# Esquem_tico_01.net
KiCad netlist of a schematic drawn in EAGLE
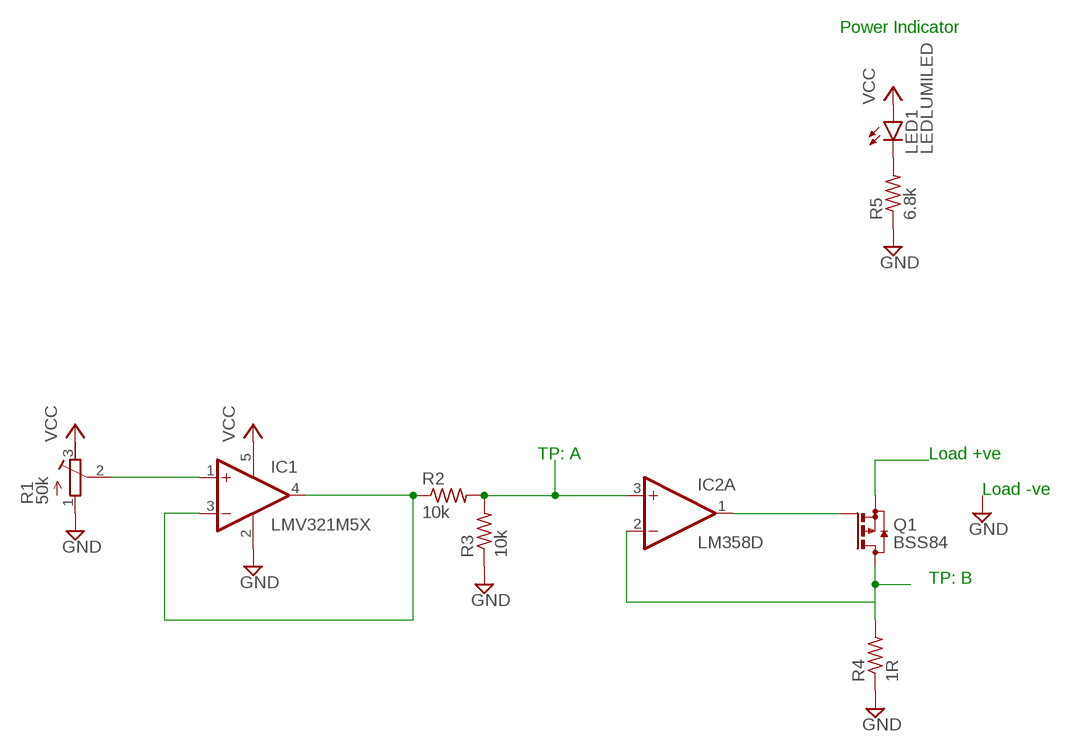
[diagram p0: schematic, sheet 1]

(export (version "E")
  (design (tool "Eeschema 10.0.6"))
  (components
    (comp (ref "IC1")
      (value "LMV321M5X")
      (footprint "eagle-import:SOT23-5")
      (libsource (lib "eagle-import") (part "LMV321?M5X"))
    )
    (comp (ref "IC2")
      (value "LM358D")
      (footprint "eagle-import:SO08")
      (libsource (lib "eagle-import") (part "LM358D"))
    )
    (comp (ref "LED1")
      (value "LEDLUMILED")
      (footprint "eagle-import:LUMILED")
      (libsource (lib "eagle-import") (part "LEDLUMILED"))
    )
    (comp (ref "Q1")
      (value "BSS84")
      (footprint "eagle-import:SOT23")
      (libsource (lib "eagle-import") (part "BSS84"))
    )
    (comp (ref "R1")
      (value "50k")
      (footprint "eagle-import:RTRIM3339P")
      (libsource (lib "eagle-import") (part "R-TRIMM3339P"))
    )
    (comp (ref "R2")
      (value "10k")
      (footprint "eagle-import:0207_10")
      (libsource (lib "eagle-import") (part "R-US_0207/10"))
    )
    (comp (ref "R3")
      (value "10k")
      (footprint "eagle-import:0207_10")
      (libsource (lib "eagle-import") (part "R-US_0207/10"))
    )
    (comp (ref "R4")
      (value "1R")
      (footprint "eagle-import:0207_10")
      (libsource (lib "eagle-import") (part "R-US_0207/10"))
    )
    (comp (ref "R5")
      (value "6.8k")
      (footprint "eagle-import:0207_10")
      (libsource (lib "eagle-import") (part "R-US_0207/10"))
    )
  )
  (nets
    (net (code "1") (name "GND") (class "Default")
      (node (ref "IC1") (pin "2") (pinfunction "V-_2") (pintype "power_in"))
      (node (ref "R1") (pin "1") (pinfunction "A_1") (pintype "passive"))
      (node (ref "R3") (pin "1") (pinfunction "1_1") (pintype "passive"))
      (node (ref "R4") (pin "1") (pinfunction "1_1") (pintype "passive"))
      (node (ref "R5") (pin "1") (pinfunction "1_1") (pintype "passive"))
    )
    (net (code "2") (name "Net-(IC1-+IN)") (class "Default")
      (node (ref "IC1") (pin "1") (pinfunction "+IN_1") (pintype "input"))
      (node (ref "R1") (pin "2") (pinfunction "S_2") (pintype "passive"))
    )
    (net (code "3") (name "Net-(IC1--IN)") (class "Default")
      (node (ref "IC1") (pin "3") (pinfunction "-IN_3") (pintype "input"))
      (node (ref "IC1") (pin "4") (pinfunction "OUT_4") (pintype "output"))
      (node (ref "R2") (pin "1") (pinfunction "1_1") (pintype "passive"))
    )
    (net (code "4") (name "Net-(IC2A-+IN)") (class "Default")
      (node (ref "IC2") (pin "3") (pinfunction "+IN_3") (pintype "input"))
      (node (ref "R2") (pin "2") (pinfunction "2_2") (pintype "passive"))
      (node (ref "R3") (pin "2") (pinfunction "2_2") (pintype "passive"))
    )
    (net (code "5") (name "Net-(IC2A-OUT)") (class "Default")
      (node (ref "IC2") (pin "1") (pinfunction "OUT_1") (pintype "output"))
      (node (ref "Q1") (pin "1") (pinfunction "G_1") (pintype "passive"))
    )
    (net (code "6") (name "Net-(LED1-C)") (class "Default")
      (node (ref "LED1") (pin "4-") (pinfunction "C_4-") (pintype "passive"))
      (node (ref "R5") (pin "2") (pinfunction "2_2") (pintype "passive"))
    )
    (net (code "7") (name "Net-(Q1-D)") (class "Default")
      (node (ref "Q1") (pin "3") (pinfunction "D_3") (pintype "passive"))
      (node (ref "R4") (pin "2") (pinfunction "2_2") (pintype "passive"))
    )
    (net (code "8") (name "VCC") (class "Default")
      (node (ref "IC1") (pin "5") (pinfunction "V+_5") (pintype "power_in"))
      (node (ref "LED1") (pin "2+") (pinfunction "A_2+") (pintype "passive"))
      (node (ref "R1") (pin "3") (pinfunction "E_3") (pintype "passive"))
    )
    (net (code "9") (name "unconnected-(IC2A--IN-Pad2)") (class "Default")
      (node (ref "IC2") (pin "2") (pinfunction "-IN_2") (pintype "input"))
    )
    (net (code "10") (name "unconnected-(Q1-S-Pad2)") (class "Default")
      (node (ref "Q1") (pin "2") (pinfunction "S_2") (pintype "passive"))
    )
  )
)
